# 3DSensor_Magnet.net
KiCad netlist of a schematic drawn in Altium Designer
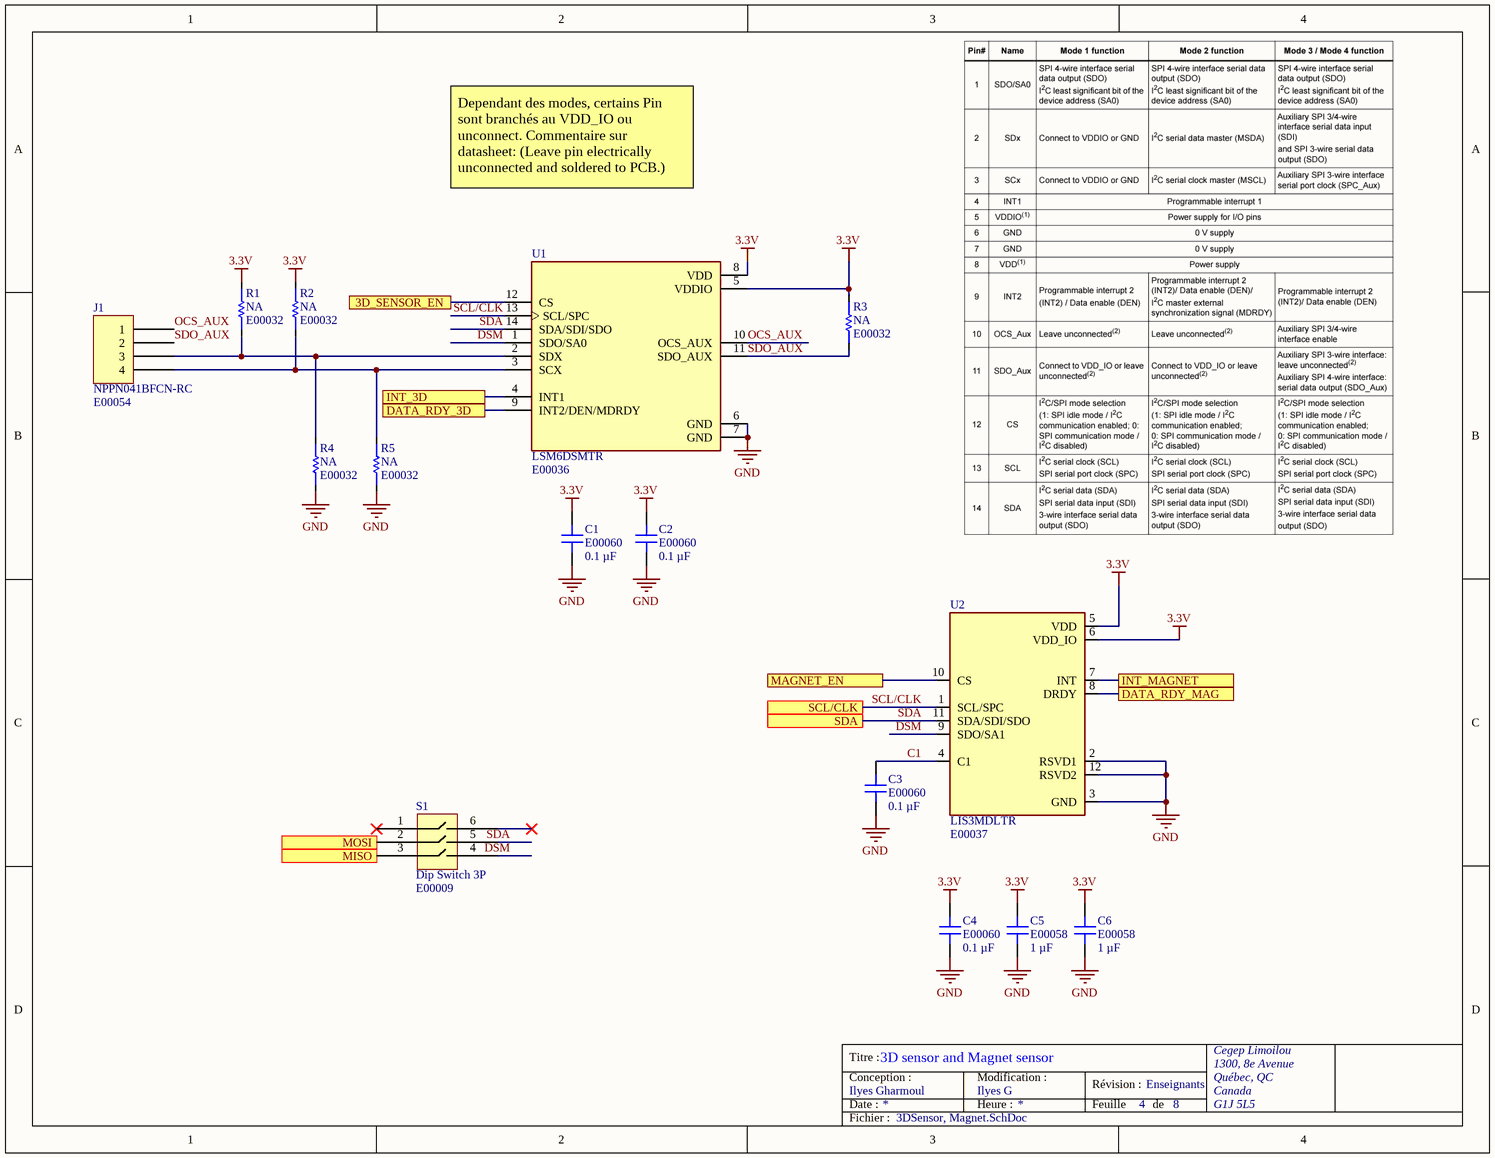
[diagram p0: 3DSensor, Magnet.SchDoc]

(export (version "E")
  (design (tool "Eeschema 10.0.6"))
  (components
    (comp (ref "C1")
      (value "0.1 µF")
      (footprint "CAP 0603")
      (description "CAP CER 0.1UF 50V X7R 0603")
      (fields
        (field (name "MANUFACTURER") "KEMET")
        (field (name "TOLERANCE") "±10%")
        (field (name "ADAM INVENTORY NUMBER 1") "E00060")
      )
      (libsource (lib "ADAM LIBRARY") (part "CAP CER 0.1UF 50V X7R 0603"))
    )
    (comp (ref "C2")
      (value "0.1 µF")
      (footprint "CAP 0603")
      (description "CAP CER 0.1UF 50V X7R 0603")
      (fields
        (field (name "MANUFACTURER") "KEMET")
        (field (name "TOLERANCE") "±10%")
        (field (name "ADAM INVENTORY NUMBER 1") "E00060")
      )
      (libsource (lib "ADAM LIBRARY") (part "CAP CER 0.1UF 50V X7R 0603"))
    )
    (comp (ref "C3")
      (value "0.1 µF")
      (footprint "CAP 0603")
      (description "CAP CER 0.1UF 50V X7R 0603")
      (fields
        (field (name "MANUFACTURER") "KEMET")
        (field (name "TOLERANCE") "±10%")
        (field (name "ADAM INVENTORY NUMBER 1") "E00060")
      )
      (libsource (lib "ADAM LIBRARY") (part "CAP CER 0.1UF 50V X7R 0603"))
    )
    (comp (ref "C4")
      (value "0.1 µF")
      (footprint "CAP 0603")
      (description "CAP CER 0.1UF 50V X7R 0603")
      (fields
        (field (name "MANUFACTURER") "KEMET")
        (field (name "TOLERANCE") "±10%")
        (field (name "ADAM INVENTORY NUMBER 1") "E00060")
      )
      (libsource (lib "ADAM LIBRARY") (part "CAP CER 0.1UF 50V X7R 0603"))
    )
    (comp (ref "C5")
      (value "1 µF")
      (footprint "CAP 0603")
      (description "CAP CER 1UF 16V X7R 0603")
      (fields
        (field (name "MANUFACTURER") "KEMET")
        (field (name "TOLERANCE") "±10%")
        (field (name "ADAM INVENTORY NUMBER 1") "E00058")
      )
      (libsource (lib "ADAM LIBRARY") (part "CAP CER 1UF 16V X7R 0603"))
    )
    (comp (ref "C6")
      (value "1 µF")
      (footprint "CAP 0603")
      (description "CAP CER 1UF 16V X7R 0603")
      (fields
        (field (name "MANUFACTURER") "KEMET")
        (field (name "TOLERANCE") "±10%")
        (field (name "ADAM INVENTORY NUMBER 1") "E00058")
      )
      (libsource (lib "ADAM LIBRARY") (part "CAP CER 1UF 16V X7R 0603"))
    )
    (comp (ref "J1")
      (value "NPPN041BFCN-RC")
      (footprint "CONN FEM HEADER 4PIN")
      (description "CONN HDR 4POS 0.079 GOLD")
      (fields
        (field (name "MANUFACTURER") "Sullins Connector Solutions")
        (field (name "ADAM INVENTORY NUMBER 1") "E00054")
      )
      (libsource (lib "ADAM LIBRARY") (part "CONN FEM HEADER 4POS"))
    )
    (comp (ref "R1")
      (value "NA")
      (footprint "RES 0603")
      (description "No resistance, just in case")
      (fields (field (name "ADAM INVENTORY NUMBER 1") "E00032"))
      (libsource (lib "ADAM LIBRARY") (part "NA Res 0603"))
    )
    (comp (ref "R2")
      (value "NA")
      (footprint "RES 0603")
      (description "No resistance, just in case")
      (fields (field (name "ADAM INVENTORY NUMBER 1") "E00032"))
      (libsource (lib "ADAM LIBRARY") (part "NA Res 0603"))
    )
    (comp (ref "R3")
      (value "NA")
      (footprint "RES 0603")
      (description "No resistance, just in case")
      (fields (field (name "ADAM INVENTORY NUMBER 1") "E00032"))
      (libsource (lib "ADAM LIBRARY") (part "NA Res 0603"))
    )
    (comp (ref "R4")
      (value "NA")
      (footprint "RES 0603")
      (description "No resistance, just in case")
      (fields (field (name "ADAM INVENTORY NUMBER 1") "E00032"))
      (libsource (lib "ADAM LIBRARY") (part "NA Res 0603"))
    )
    (comp (ref "R5")
      (value "NA")
      (footprint "RES 0603")
      (description "No resistance, just in case")
      (fields (field (name "ADAM INVENTORY NUMBER 1") "E00032"))
      (libsource (lib "ADAM LIBRARY") (part "NA Res 0603"))
    )
    (comp (ref "S1")
      (value "Dip Switch 3P")
      (footprint "DIPSWITCH SMD 3P")
      (description "Dip Switch SPST 3 Position Surface Mount Slide (Standard) Actuator 25mA 24VDC")
      (fields (field (name "MANUFACTURER") "CUI") (field (name "ADAM INVENTORY NUMBER 1") "E00009"))
      (libsource (lib "ADAM LIBRARY") (part "Dip Switch 3P"))
    )
    (comp (ref "U1")
      (value "LSM6DSMTR")
      (footprint "PQFN50P300X250X86-14N")
      (description "Accelerometer, Gyroscope, Temperature, 6 Axis Sensor I²C, SPI Output")
      (fields (field (name "ADAM INVENTORY NUMBER 1") "E00036"))
      (libsource (lib "ADAM LIBRARY") (part "LSM6DSMTR"))
    )
    (comp (ref "U2")
      (value "LIS3MDLTR")
      (footprint "XDCR_LIS3MDLTR")
      (description "Magnetoresistive Sensor X, Y, Z Axis 12-LGA (2x2)")
      (fields (field (name "ADAM INVENTORY NUMBER 1") "E00037"))
      (libsource (lib "ADAM LIBRARY") (part "LIS3MDLTR"))
    )
  )
  (nets
    (net (code "1") (name "/3D_SENSOR_EN") (class "Default")
      (node (ref "U1") (pin "12") (pinfunction "CS_12") (pintype "passive"))
    )
    (net (code "2") (name "/C1") (class "Default")
      (node (ref "C3") (pin "2") (pinfunction "2_2") (pintype "passive"))
      (node (ref "U2") (pin "4") (pinfunction "C1_4") (pintype "passive"))
    )
    (net (code "3") (name "/DATA_RDY_3D") (class "Default")
      (node (ref "U1") (pin "9") (pinfunction "INT2/DEN/MDRDY_9") (pintype "passive"))
    )
    (net (code "4") (name "/DATA_RDY_MAG") (class "Default")
      (node (ref "U2") (pin "8") (pinfunction "DRDY_8") (pintype "passive"))
    )
    (net (code "5") (name "/DSM") (class "Default")
      (node (ref "S1") (pin "4") (pinfunction "4_4") (pintype "passive"))
      (node (ref "U1") (pin "1") (pinfunction "SDO/SA0_1") (pintype "passive"))
      (node (ref "U2") (pin "9") (pinfunction "SDO/SA1_9") (pintype "passive"))
    )
    (net (code "6") (name "/INT_3D") (class "Default")
      (node (ref "U1") (pin "4") (pinfunction "INT1_4") (pintype "passive"))
    )
    (net (code "7") (name "/INT_MAGNET") (class "Default")
      (node (ref "U2") (pin "7") (pinfunction "INT_7") (pintype "passive"))
    )
    (net (code "8") (name "/MAGNET_EN") (class "Default")
      (node (ref "U2") (pin "10") (pinfunction "CS_10") (pintype "passive"))
    )
    (net (code "9") (name "/MISO") (class "Default")
      (node (ref "S1") (pin "3") (pinfunction "3_3") (pintype "passive"))
    )
    (net (code "10") (name "/MOSI") (class "Default")
      (node (ref "S1") (pin "2") (pinfunction "2_2") (pintype "passive"))
    )
    (net (code "11") (name "/OCS_AUX") (class "Default")
      (node (ref "J1") (pin "1") (pinfunction "1_1") (pintype "passive"))
      (node (ref "U1") (pin "10") (pinfunction "OCS_AUX_10") (pintype "passive"))
    )
    (net (code "12") (name "/SCL{slash}CLK") (class "Default")
      (node (ref "U1") (pin "13") (pinfunction "SCL/SPC_13") (pintype "passive"))
      (node (ref "U2") (pin "1") (pinfunction "SCL/SPC_1") (pintype "passive"))
    )
    (net (code "13") (name "/SDA") (class "Default")
      (node (ref "S1") (pin "5") (pinfunction "5_5") (pintype "passive"))
      (node (ref "U1") (pin "14") (pinfunction "SDA/SDI/SDO_14") (pintype "passive"))
      (node (ref "U2") (pin "11") (pinfunction "SDA/SDI/SDO_11") (pintype "passive"))
    )
    (net (code "14") (name "/SDO_AUX") (class "Default")
      (node (ref "J1") (pin "2") (pinfunction "2_2") (pintype "passive"))
      (node (ref "R3") (pin "1") (pinfunction "1_1") (pintype "passive"))
      (node (ref "U1") (pin "11") (pinfunction "SDO_AUX_11") (pintype "passive"))
    )
    (net (code "15") (name "3.3V") (class "Default")
      (node (ref "C1") (pin "2") (pinfunction "2_2") (pintype "passive"))
      (node (ref "C2") (pin "2") (pinfunction "2_2") (pintype "passive"))
      (node (ref "C4") (pin "2") (pinfunction "2_2") (pintype "passive"))
      (node (ref "C5") (pin "2") (pinfunction "2_2") (pintype "passive"))
      (node (ref "C6") (pin "2") (pinfunction "2_2") (pintype "passive"))
      (node (ref "R1") (pin "2") (pinfunction "2_2") (pintype "passive"))
      (node (ref "R2") (pin "2") (pinfunction "2_2") (pintype "passive"))
      (node (ref "R3") (pin "2") (pinfunction "2_2") (pintype "passive"))
      (node (ref "U1") (pin "5") (pinfunction "VDDIO_5") (pintype "passive"))
      (node (ref "U1") (pin "8") (pinfunction "VDD_8") (pintype "passive"))
      (node (ref "U2") (pin "5") (pinfunction "VDD_5") (pintype "passive"))
      (node (ref "U2") (pin "6") (pinfunction "VDD_IO_6") (pintype "passive"))
    )
    (net (code "16") (name "GND") (class "Default")
      (node (ref "C1") (pin "1") (pinfunction "1_1") (pintype "passive"))
      (node (ref "C2") (pin "1") (pinfunction "1_1") (pintype "passive"))
      (node (ref "C3") (pin "1") (pinfunction "1_1") (pintype "passive"))
      (node (ref "C4") (pin "1") (pinfunction "1_1") (pintype "passive"))
      (node (ref "C5") (pin "1") (pinfunction "1_1") (pintype "passive"))
      (node (ref "C6") (pin "1") (pinfunction "1_1") (pintype "passive"))
      (node (ref "R4") (pin "1") (pinfunction "1_1") (pintype "passive"))
      (node (ref "R5") (pin "1") (pinfunction "1_1") (pintype "passive"))
      (node (ref "U1") (pin "6") (pinfunction "GND_6") (pintype "passive"))
      (node (ref "U1") (pin "7") (pinfunction "GND_7") (pintype "passive"))
      (node (ref "U2") (pin "12") (pinfunction "RSVD2_12") (pintype "passive"))
      (node (ref "U2") (pin "2") (pinfunction "RSVD1_2") (pintype "passive"))
      (node (ref "U2") (pin "3") (pinfunction "GND_3") (pintype "passive"))
    )
    (net (code "17") (name "Net-(U1-SCX)") (class "Default")
      (node (ref "J1") (pin "4") (pinfunction "4_4") (pintype "passive"))
      (node (ref "R2") (pin "1") (pinfunction "1_1") (pintype "passive"))
      (node (ref "R5") (pin "2") (pinfunction "2_2") (pintype "passive"))
      (node (ref "U1") (pin "3") (pinfunction "SCX_3") (pintype "passive"))
    )
    (net (code "18") (name "Net-(U1-SDX)") (class "Default")
      (node (ref "J1") (pin "3") (pinfunction "3_3") (pintype "passive"))
      (node (ref "R1") (pin "1") (pinfunction "1_1") (pintype "passive"))
      (node (ref "R4") (pin "2") (pinfunction "2_2") (pintype "passive"))
      (node (ref "U1") (pin "2") (pinfunction "SDX_2") (pintype "passive"))
    )
    (net (code "19") (name "unconnected-(S1-Pad1)") (class "Default")
      (node (ref "S1") (pin "1") (pinfunction "1_1") (pintype "passive+no_connect"))
    )
    (net (code "20") (name "unconnected-(S1-Pad6)") (class "Default")
      (node (ref "S1") (pin "6") (pinfunction "6_6") (pintype "passive+no_connect"))
    )
  )
)
